# SIK-DIP-board.net
KiCad netlist of a schematic drawn in EAGLE
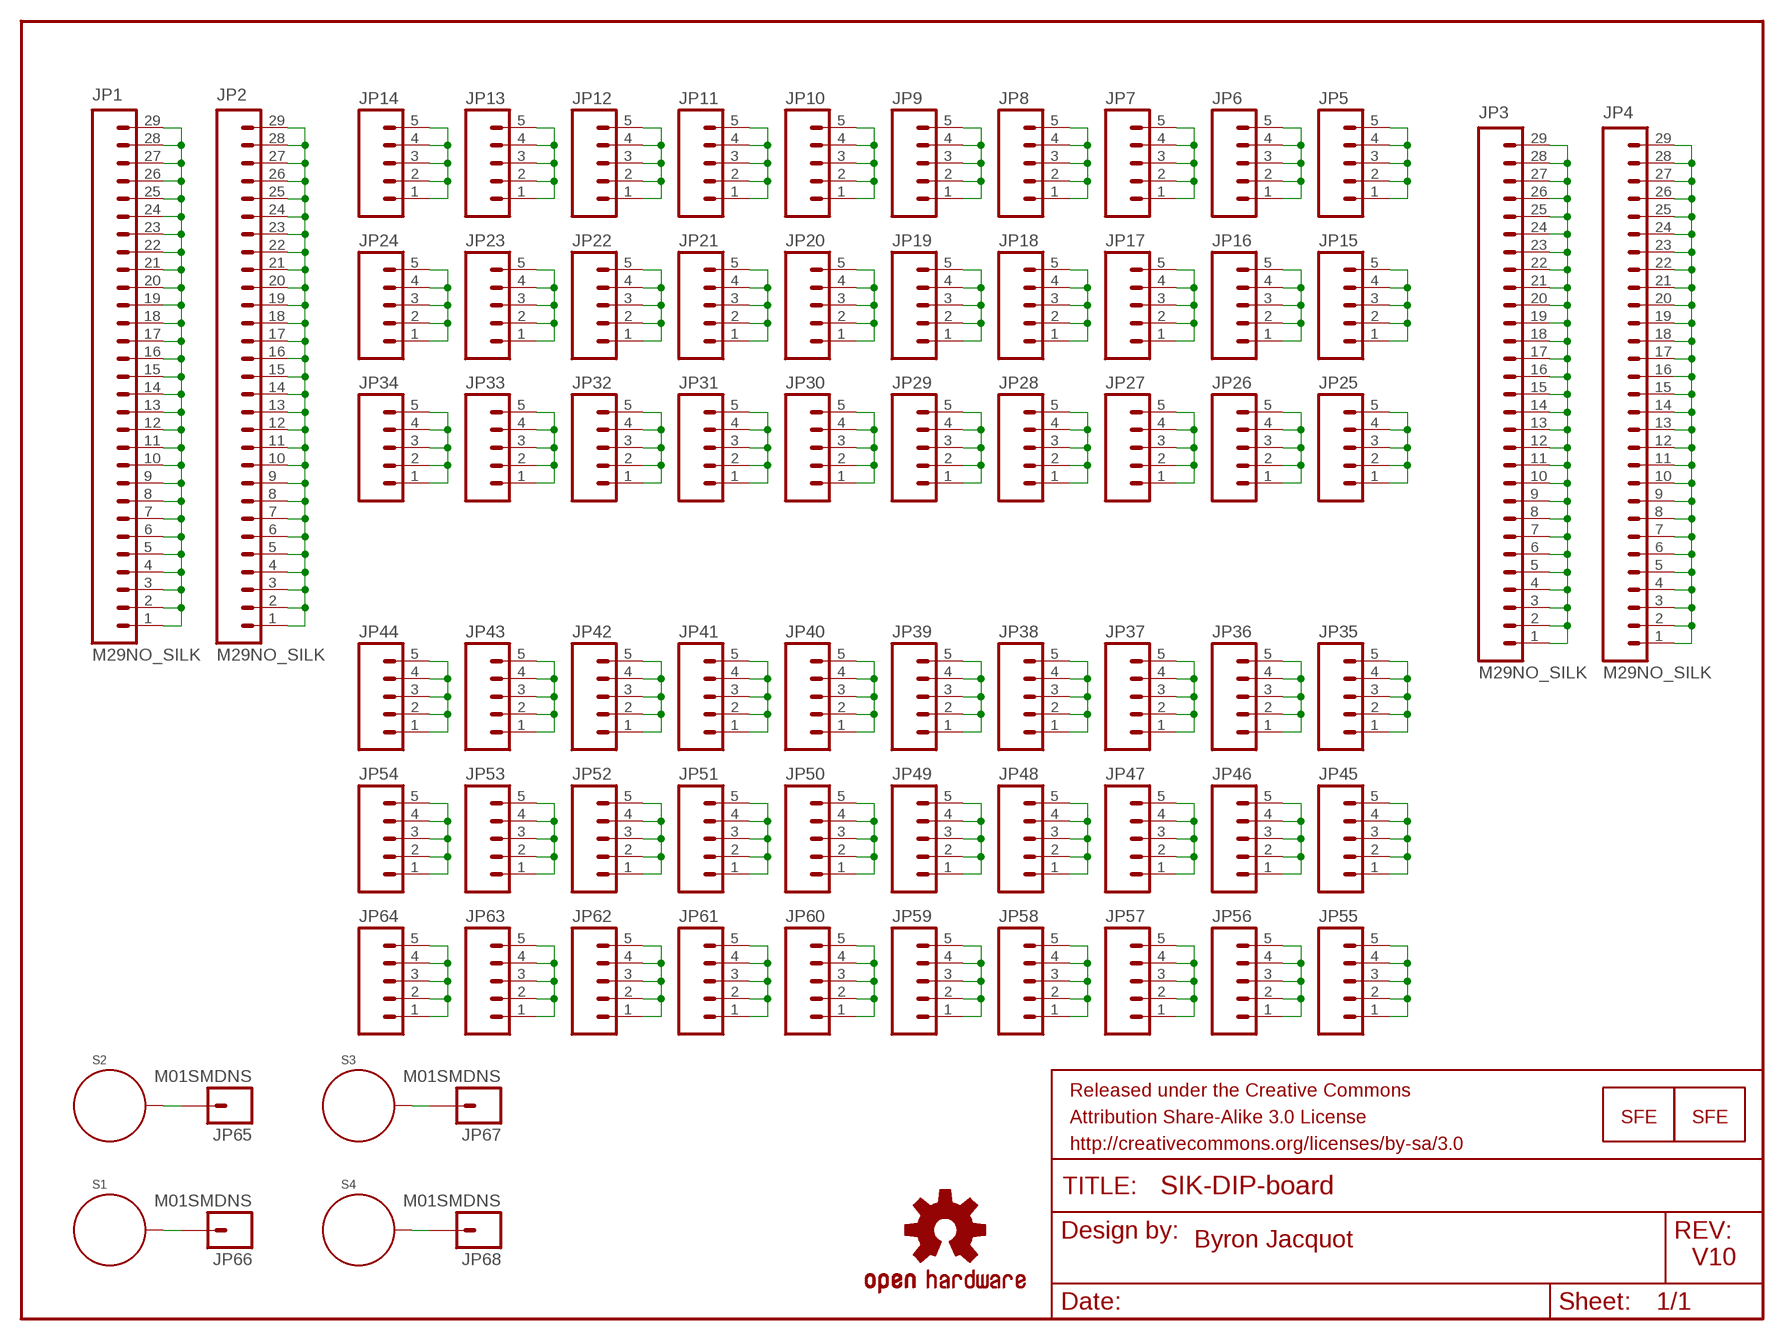
[diagram p0: schematic, sheet 1]

(export (version "E")
  (design (tool "Eeschema 10.0.6"))
  (components
    (comp (ref "FRAME1")
      (value "FRAME-LETTER")
      (footprint "eagle-import:CREATIVE_COMMONS")
      (libsource (lib "eagle-import") (part "FRAME-LETTER"))
    )
    (comp (ref "JP1")
      (value "M29NO_SILK")
      (footprint "eagle-import:1X29_NO_SILK")
      (libsource (lib "eagle-import") (part "M29NO_SILK"))
    )
    (comp (ref "JP2")
      (value "M29NO_SILK")
      (footprint "eagle-import:1X29_NO_SILK")
      (libsource (lib "eagle-import") (part "M29NO_SILK"))
    )
    (comp (ref "JP3")
      (value "M29NO_SILK")
      (footprint "eagle-import:1X29_NO_SILK")
      (libsource (lib "eagle-import") (part "M29NO_SILK"))
    )
    (comp (ref "JP4")
      (value "M29NO_SILK")
      (footprint "eagle-import:1X29_NO_SILK")
      (libsource (lib "eagle-import") (part "M29NO_SILK"))
    )
    (comp (ref "JP5")
      (value "M05NO_SILK")
      (footprint "eagle-import:1X05_NO_SILK")
      (libsource (lib "eagle-import") (part "M05NO_SILK"))
    )
    (comp (ref "JP6")
      (value "M05NO_SILK")
      (footprint "eagle-import:1X05_NO_SILK")
      (libsource (lib "eagle-import") (part "M05NO_SILK"))
    )
    (comp (ref "JP7")
      (value "M05NO_SILK")
      (footprint "eagle-import:1X05_NO_SILK")
      (libsource (lib "eagle-import") (part "M05NO_SILK"))
    )
    (comp (ref "JP8")
      (value "M05NO_SILK")
      (footprint "eagle-import:1X05_NO_SILK")
      (libsource (lib "eagle-import") (part "M05NO_SILK"))
    )
    (comp (ref "JP9")
      (value "M05NO_SILK")
      (footprint "eagle-import:1X05_NO_SILK")
      (libsource (lib "eagle-import") (part "M05NO_SILK"))
    )
    (comp (ref "JP10")
      (value "M05NO_SILK")
      (footprint "eagle-import:1X05_NO_SILK")
      (libsource (lib "eagle-import") (part "M05NO_SILK"))
    )
    (comp (ref "JP11")
      (value "M05NO_SILK")
      (footprint "eagle-import:1X05_NO_SILK")
      (libsource (lib "eagle-import") (part "M05NO_SILK"))
    )
    (comp (ref "JP12")
      (value "M05NO_SILK")
      (footprint "eagle-import:1X05_NO_SILK")
      (libsource (lib "eagle-import") (part "M05NO_SILK"))
    )
    (comp (ref "JP13")
      (value "M05NO_SILK")
      (footprint "eagle-import:1X05_NO_SILK")
      (libsource (lib "eagle-import") (part "M05NO_SILK"))
    )
    (comp (ref "JP14")
      (value "M05NO_SILK")
      (footprint "eagle-import:1X05_NO_SILK")
      (libsource (lib "eagle-import") (part "M05NO_SILK"))
    )
    (comp (ref "JP15")
      (value "M05NO_SILK")
      (footprint "eagle-import:1X05_NO_SILK")
      (libsource (lib "eagle-import") (part "M05NO_SILK"))
    )
    (comp (ref "JP16")
      (value "M05NO_SILK")
      (footprint "eagle-import:1X05_NO_SILK")
      (libsource (lib "eagle-import") (part "M05NO_SILK"))
    )
    (comp (ref "JP17")
      (value "M05NO_SILK")
      (footprint "eagle-import:1X05_NO_SILK")
      (libsource (lib "eagle-import") (part "M05NO_SILK"))
    )
    (comp (ref "JP18")
      (value "M05NO_SILK")
      (footprint "eagle-import:1X05_NO_SILK")
      (libsource (lib "eagle-import") (part "M05NO_SILK"))
    )
    (comp (ref "JP19")
      (value "M05NO_SILK")
      (footprint "eagle-import:1X05_NO_SILK")
      (libsource (lib "eagle-import") (part "M05NO_SILK"))
    )
    (comp (ref "JP20")
      (value "M05NO_SILK")
      (footprint "eagle-import:1X05_NO_SILK")
      (libsource (lib "eagle-import") (part "M05NO_SILK"))
    )
    (comp (ref "JP21")
      (value "M05NO_SILK")
      (footprint "eagle-import:1X05_NO_SILK")
      (libsource (lib "eagle-import") (part "M05NO_SILK"))
    )
    (comp (ref "JP22")
      (value "M05NO_SILK")
      (footprint "eagle-import:1X05_NO_SILK")
      (libsource (lib "eagle-import") (part "M05NO_SILK"))
    )
    (comp (ref "JP23")
      (value "M05NO_SILK")
      (footprint "eagle-import:1X05_NO_SILK")
      (libsource (lib "eagle-import") (part "M05NO_SILK"))
    )
    (comp (ref "JP24")
      (value "M05NO_SILK")
      (footprint "eagle-import:1X05_NO_SILK")
      (libsource (lib "eagle-import") (part "M05NO_SILK"))
    )
    (comp (ref "JP25")
      (value "M05NO_SILK")
      (footprint "eagle-import:1X05_NO_SILK")
      (libsource (lib "eagle-import") (part "M05NO_SILK"))
    )
    (comp (ref "JP26")
      (value "M05NO_SILK")
      (footprint "eagle-import:1X05_NO_SILK")
      (libsource (lib "eagle-import") (part "M05NO_SILK"))
    )
    (comp (ref "JP27")
      (value "M05NO_SILK")
      (footprint "eagle-import:1X05_NO_SILK")
      (libsource (lib "eagle-import") (part "M05NO_SILK"))
    )
    (comp (ref "JP28")
      (value "M05NO_SILK")
      (footprint "eagle-import:1X05_NO_SILK")
      (libsource (lib "eagle-import") (part "M05NO_SILK"))
    )
    (comp (ref "JP29")
      (value "M05NO_SILK")
      (footprint "eagle-import:1X05_NO_SILK")
      (libsource (lib "eagle-import") (part "M05NO_SILK"))
    )
    (comp (ref "JP30")
      (value "M05NO_SILK")
      (footprint "eagle-import:1X05_NO_SILK")
      (libsource (lib "eagle-import") (part "M05NO_SILK"))
    )
    (comp (ref "JP31")
      (value "M05NO_SILK")
      (footprint "eagle-import:1X05_NO_SILK")
      (libsource (lib "eagle-import") (part "M05NO_SILK"))
    )
    (comp (ref "JP32")
      (value "M05NO_SILK")
      (footprint "eagle-import:1X05_NO_SILK")
      (libsource (lib "eagle-import") (part "M05NO_SILK"))
    )
    (comp (ref "JP33")
      (value "M05NO_SILK")
      (footprint "eagle-import:1X05_NO_SILK")
      (libsource (lib "eagle-import") (part "M05NO_SILK"))
    )
    (comp (ref "JP34")
      (value "M05NO_SILK")
      (footprint "eagle-import:1X05_NO_SILK")
      (libsource (lib "eagle-import") (part "M05NO_SILK"))
    )
    (comp (ref "JP35")
      (value "M05NO_SILK")
      (footprint "eagle-import:1X05_NO_SILK")
      (libsource (lib "eagle-import") (part "M05NO_SILK"))
    )
    (comp (ref "JP36")
      (value "M05NO_SILK")
      (footprint "eagle-import:1X05_NO_SILK")
      (libsource (lib "eagle-import") (part "M05NO_SILK"))
    )
    (comp (ref "JP37")
      (value "M05NO_SILK")
      (footprint "eagle-import:1X05_NO_SILK")
      (libsource (lib "eagle-import") (part "M05NO_SILK"))
    )
    (comp (ref "JP38")
      (value "M05NO_SILK")
      (footprint "eagle-import:1X05_NO_SILK")
      (libsource (lib "eagle-import") (part "M05NO_SILK"))
    )
    (comp (ref "JP39")
      (value "M05NO_SILK")
      (footprint "eagle-import:1X05_NO_SILK")
      (libsource (lib "eagle-import") (part "M05NO_SILK"))
    )
    (comp (ref "JP40")
      (value "M05NO_SILK")
      (footprint "eagle-import:1X05_NO_SILK")
      (libsource (lib "eagle-import") (part "M05NO_SILK"))
    )
    (comp (ref "JP41")
      (value "M05NO_SILK")
      (footprint "eagle-import:1X05_NO_SILK")
      (libsource (lib "eagle-import") (part "M05NO_SILK"))
    )
    (comp (ref "JP42")
      (value "M05NO_SILK")
      (footprint "eagle-import:1X05_NO_SILK")
      (libsource (lib "eagle-import") (part "M05NO_SILK"))
    )
    (comp (ref "JP43")
      (value "M05NO_SILK")
      (footprint "eagle-import:1X05_NO_SILK")
      (libsource (lib "eagle-import") (part "M05NO_SILK"))
    )
    (comp (ref "JP44")
      (value "M05NO_SILK")
      (footprint "eagle-import:1X05_NO_SILK")
      (libsource (lib "eagle-import") (part "M05NO_SILK"))
    )
    (comp (ref "JP45")
      (value "M05NO_SILK")
      (footprint "eagle-import:1X05_NO_SILK")
      (libsource (lib "eagle-import") (part "M05NO_SILK"))
    )
    (comp (ref "JP46")
      (value "M05NO_SILK")
      (footprint "eagle-import:1X05_NO_SILK")
      (libsource (lib "eagle-import") (part "M05NO_SILK"))
    )
    (comp (ref "JP47")
      (value "M05NO_SILK")
      (footprint "eagle-import:1X05_NO_SILK")
      (libsource (lib "eagle-import") (part "M05NO_SILK"))
    )
    (comp (ref "JP48")
      (value "M05NO_SILK")
      (footprint "eagle-import:1X05_NO_SILK")
      (libsource (lib "eagle-import") (part "M05NO_SILK"))
    )
    (comp (ref "JP49")
      (value "M05NO_SILK")
      (footprint "eagle-import:1X05_NO_SILK")
      (libsource (lib "eagle-import") (part "M05NO_SILK"))
    )
    (comp (ref "JP50")
      (value "M05NO_SILK")
      (footprint "eagle-import:1X05_NO_SILK")
      (libsource (lib "eagle-import") (part "M05NO_SILK"))
    )
    (comp (ref "JP51")
      (value "M05NO_SILK")
      (footprint "eagle-import:1X05_NO_SILK")
      (libsource (lib "eagle-import") (part "M05NO_SILK"))
    )
    (comp (ref "JP52")
      (value "M05NO_SILK")
      (footprint "eagle-import:1X05_NO_SILK")
      (libsource (lib "eagle-import") (part "M05NO_SILK"))
    )
    (comp (ref "JP53")
      (value "M05NO_SILK")
      (footprint "eagle-import:1X05_NO_SILK")
      (libsource (lib "eagle-import") (part "M05NO_SILK"))
    )
    (comp (ref "JP54")
      (value "M05NO_SILK")
      (footprint "eagle-import:1X05_NO_SILK")
      (libsource (lib "eagle-import") (part "M05NO_SILK"))
    )
    (comp (ref "JP55")
      (value "M05NO_SILK")
      (footprint "eagle-import:1X05_NO_SILK")
      (libsource (lib "eagle-import") (part "M05NO_SILK"))
    )
    (comp (ref "JP56")
      (value "M05NO_SILK")
      (footprint "eagle-import:1X05_NO_SILK")
      (libsource (lib "eagle-import") (part "M05NO_SILK"))
    )
    (comp (ref "JP57")
      (value "M05NO_SILK")
      (footprint "eagle-import:1X05_NO_SILK")
      (libsource (lib "eagle-import") (part "M05NO_SILK"))
    )
    (comp (ref "JP58")
      (value "M05NO_SILK")
      (footprint "eagle-import:1X05_NO_SILK")
      (libsource (lib "eagle-import") (part "M05NO_SILK"))
    )
    (comp (ref "JP59")
      (value "M05NO_SILK")
      (footprint "eagle-import:1X05_NO_SILK")
      (libsource (lib "eagle-import") (part "M05NO_SILK"))
    )
    (comp (ref "JP60")
      (value "M05NO_SILK")
      (footprint "eagle-import:1X05_NO_SILK")
      (libsource (lib "eagle-import") (part "M05NO_SILK"))
    )
    (comp (ref "JP61")
      (value "M05NO_SILK")
      (footprint "eagle-import:1X05_NO_SILK")
      (libsource (lib "eagle-import") (part "M05NO_SILK"))
    )
    (comp (ref "JP62")
      (value "M05NO_SILK")
      (footprint "eagle-import:1X05_NO_SILK")
      (libsource (lib "eagle-import") (part "M05NO_SILK"))
    )
    (comp (ref "JP63")
      (value "M05NO_SILK")
      (footprint "eagle-import:1X05_NO_SILK")
      (libsource (lib "eagle-import") (part "M05NO_SILK"))
    )
    (comp (ref "JP64")
      (value "M05NO_SILK")
      (footprint "eagle-import:1X05_NO_SILK")
      (libsource (lib "eagle-import") (part "M05NO_SILK"))
    )
    (comp (ref "JP65")
      (value "M01SMDNS")
      (footprint "eagle-import:1X01NS")
      (libsource (lib "eagle-import") (part "M01SMDNS"))
    )
    (comp (ref "JP66")
      (value "M01SMDNS")
      (footprint "eagle-import:1X01NS")
      (libsource (lib "eagle-import") (part "M01SMDNS"))
    )
    (comp (ref "JP67")
      (value "M01SMDNS")
      (footprint "eagle-import:1X01NS")
      (libsource (lib "eagle-import") (part "M01SMDNS"))
    )
    (comp (ref "JP68")
      (value "M01SMDNS")
      (footprint "eagle-import:1X01NS")
      (libsource (lib "eagle-import") (part "M01SMDNS"))
    )
    (comp (ref "LOGO1")
      (value "LOGO-SFECP")
      (footprint "eagle-import:SFE-LOGO-FLAME-COPPER")
      (libsource (lib "eagle-import") (part "LOGO-SFECP"))
    )
    (comp (ref "LOGO2")
      (value "LOGO-SFENEW")
      (footprint "eagle-import:SFE-NEW-WEBLOGO")
      (libsource (lib "eagle-import") (part "LOGO-SFENEW"))
    )
    (comp (ref "LOGO3")
      (value "OSHW-LOGOS")
      (footprint "eagle-import:OSHW-LOGO-S")
      (libsource (lib "eagle-import") (part "OSHW-LOGOS"))
    )
    (comp (ref "S1")
      (value "STANDOFF_ELECTRICAL")
      (footprint "eagle-import:STANDOFF-ELECTRICAL")
      (libsource (lib "eagle-import") (part "STANDOFF_ELECTRICAL"))
    )
    (comp (ref "S2")
      (value "STANDOFF_ELECTRICAL")
      (footprint "eagle-import:STANDOFF-ELECTRICAL")
      (libsource (lib "eagle-import") (part "STANDOFF_ELECTRICAL"))
    )
    (comp (ref "S3")
      (value "STANDOFF_ELECTRICAL")
      (footprint "eagle-import:STANDOFF-ELECTRICAL")
      (libsource (lib "eagle-import") (part "STANDOFF_ELECTRICAL"))
    )
    (comp (ref "S4")
      (value "STANDOFF_ELECTRICAL")
      (footprint "eagle-import:STANDOFF-ELECTRICAL")
      (libsource (lib "eagle-import") (part "STANDOFF_ELECTRICAL"))
    )
  )
  (nets
    (net (code "1") (name "Net-(JP1-Pad1)") (class "Default")
      (node (ref "JP1") (pin "1") (pinfunction "1_1") (pintype "passive"))
      (node (ref "JP1") (pin "10") (pinfunction "10_10") (pintype "passive"))
      (node (ref "JP1") (pin "11") (pinfunction "11_11") (pintype "passive"))
      (node (ref "JP1") (pin "12") (pinfunction "12_12") (pintype "passive"))
      (node (ref "JP1") (pin "13") (pinfunction "13_13") (pintype "passive"))
      (node (ref "JP1") (pin "14") (pinfunction "14_14") (pintype "passive"))
      (node (ref "JP1") (pin "15") (pinfunction "15_15") (pintype "passive"))
      (node (ref "JP1") (pin "16") (pinfunction "16_16") (pintype "passive"))
      (node (ref "JP1") (pin "17") (pinfunction "17_17") (pintype "passive"))
      (node (ref "JP1") (pin "18") (pinfunction "18_18") (pintype "passive"))
      (node (ref "JP1") (pin "19") (pinfunction "19_19") (pintype "passive"))
      (node (ref "JP1") (pin "2") (pinfunction "2_2") (pintype "passive"))
      (node (ref "JP1") (pin "20") (pinfunction "20_20") (pintype "passive"))
      (node (ref "JP1") (pin "21") (pinfunction "21_21") (pintype "passive"))
      (node (ref "JP1") (pin "22") (pinfunction "22_22") (pintype "passive"))
      (node (ref "JP1") (pin "23") (pinfunction "23_23") (pintype "passive"))
      (node (ref "JP1") (pin "24") (pinfunction "24_24") (pintype "passive"))
      (node (ref "JP1") (pin "25") (pinfunction "25_25") (pintype "passive"))
      (node (ref "JP1") (pin "26") (pinfunction "26_26") (pintype "passive"))
      (node (ref "JP1") (pin "27") (pinfunction "27_27") (pintype "passive"))
      (node (ref "JP1") (pin "28") (pinfunction "28_28") (pintype "passive"))
      (node (ref "JP1") (pin "29") (pinfunction "29_29") (pintype "passive"))
      (node (ref "JP1") (pin "3") (pinfunction "3_3") (pintype "passive"))
      (node (ref "JP1") (pin "4") (pinfunction "4_4") (pintype "passive"))
      (node (ref "JP1") (pin "5") (pinfunction "5_5") (pintype "passive"))
      (node (ref "JP1") (pin "6") (pinfunction "6_6") (pintype "passive"))
      (node (ref "JP1") (pin "7") (pinfunction "7_7") (pintype "passive"))
      (node (ref "JP1") (pin "8") (pinfunction "8_8") (pintype "passive"))
      (node (ref "JP1") (pin "9") (pinfunction "9_9") (pintype "passive"))
    )
    (net (code "2") (name "Net-(JP2-Pad1)") (class "Default")
      (node (ref "JP2") (pin "1") (pinfunction "1_1") (pintype "passive"))
      (node (ref "JP2") (pin "10") (pinfunction "10_10") (pintype "passive"))
      (node (ref "JP2") (pin "11") (pinfunction "11_11") (pintype "passive"))
      (node (ref "JP2") (pin "12") (pinfunction "12_12") (pintype "passive"))
      (node (ref "JP2") (pin "13") (pinfunction "13_13") (pintype "passive"))
      (node (ref "JP2") (pin "14") (pinfunction "14_14") (pintype "passive"))
      (node (ref "JP2") (pin "15") (pinfunction "15_15") (pintype "passive"))
      (node (ref "JP2") (pin "16") (pinfunction "16_16") (pintype "passive"))
      (node (ref "JP2") (pin "17") (pinfunction "17_17") (pintype "passive"))
      (node (ref "JP2") (pin "18") (pinfunction "18_18") (pintype "passive"))
      (node (ref "JP2") (pin "19") (pinfunction "19_19") (pintype "passive"))
      (node (ref "JP2") (pin "2") (pinfunction "2_2") (pintype "passive"))
      (node (ref "JP2") (pin "20") (pinfunction "20_20") (pintype "passive"))
      (node (ref "JP2") (pin "21") (pinfunction "21_21") (pintype "passive"))
      (node (ref "JP2") (pin "22") (pinfunction "22_22") (pintype "passive"))
      (node (ref "JP2") (pin "23") (pinfunction "23_23") (pintype "passive"))
      (node (ref "JP2") (pin "24") (pinfunction "24_24") (pintype "passive"))
      (node (ref "JP2") (pin "25") (pinfunction "25_25") (pintype "passive"))
      (node (ref "JP2") (pin "26") (pinfunction "26_26") (pintype "passive"))
      (node (ref "JP2") (pin "27") (pinfunction "27_27") (pintype "passive"))
      (node (ref "JP2") (pin "28") (pinfunction "28_28") (pintype "passive"))
      (node (ref "JP2") (pin "29") (pinfunction "29_29") (pintype "passive"))
      (node (ref "JP2") (pin "3") (pinfunction "3_3") (pintype "passive"))
      (node (ref "JP2") (pin "4") (pinfunction "4_4") (pintype "passive"))
      (node (ref "JP2") (pin "5") (pinfunction "5_5") (pintype "passive"))
      (node (ref "JP2") (pin "6") (pinfunction "6_6") (pintype "passive"))
      (node (ref "JP2") (pin "7") (pinfunction "7_7") (pintype "passive"))
      (node (ref "JP2") (pin "8") (pinfunction "8_8") (pintype "passive"))
      (node (ref "JP2") (pin "9") (pinfunction "9_9") (pintype "passive"))
    )
    (net (code "3") (name "Net-(JP3-Pad1)") (class "Default")
      (node (ref "JP3") (pin "1") (pinfunction "1_1") (pintype "passive"))
      (node (ref "JP3") (pin "10") (pinfunction "10_10") (pintype "passive"))
      (node (ref "JP3") (pin "11") (pinfunction "11_11") (pintype "passive"))
      (node (ref "JP3") (pin "12") (pinfunction "12_12") (pintype "passive"))
      (node (ref "JP3") (pin "13") (pinfunction "13_13") (pintype "passive"))
      (node (ref "JP3") (pin "14") (pinfunction "14_14") (pintype "passive"))
      (node (ref "JP3") (pin "15") (pinfunction "15_15") (pintype "passive"))
      (node (ref "JP3") (pin "16") (pinfunction "16_16") (pintype "passive"))
      (node (ref "JP3") (pin "17") (pinfunction "17_17") (pintype "passive"))
      (node (ref "JP3") (pin "18") (pinfunction "18_18") (pintype "passive"))
      (node (ref "JP3") (pin "19") (pinfunction "19_19") (pintype "passive"))
      (node (ref "JP3") (pin "2") (pinfunction "2_2") (pintype "passive"))
      (node (ref "JP3") (pin "20") (pinfunction "20_20") (pintype "passive"))
      (node (ref "JP3") (pin "21") (pinfunction "21_21") (pintype "passive"))
      (node (ref "JP3") (pin "22") (pinfunction "22_22") (pintype "passive"))
      (node (ref "JP3") (pin "23") (pinfunction "23_23") (pintype "passive"))
      (node (ref "JP3") (pin "24") (pinfunction "24_24") (pintype "passive"))
      (node (ref "JP3") (pin "25") (pinfunction "25_25") (pintype "passive"))
      (node (ref "JP3") (pin "26") (pinfunction "26_26") (pintype "passive"))
      (node (ref "JP3") (pin "27") (pinfunction "27_27") (pintype "passive"))
      (node (ref "JP3") (pin "28") (pinfunction "28_28") (pintype "passive"))
      (node (ref "JP3") (pin "29") (pinfunction "29_29") (pintype "passive"))
      (node (ref "JP3") (pin "3") (pinfunction "3_3") (pintype "passive"))
      (node (ref "JP3") (pin "4") (pinfunction "4_4") (pintype "passive"))
      (node (ref "JP3") (pin "5") (pinfunction "5_5") (pintype "passive"))
      (node (ref "JP3") (pin "6") (pinfunction "6_6") (pintype "passive"))
      (node (ref "JP3") (pin "7") (pinfunction "7_7") (pintype "passive"))
      (node (ref "JP3") (pin "8") (pinfunction "8_8") (pintype "passive"))
      (node (ref "JP3") (pin "9") (pinfunction "9_9") (pintype "passive"))
    )
    (net (code "4") (name "Net-(JP4-Pad1)") (class "Default")
      (node (ref "JP4") (pin "1") (pinfunction "1_1") (pintype "passive"))
      (node (ref "JP4") (pin "10") (pinfunction "10_10") (pintype "passive"))
      (node (ref "JP4") (pin "11") (pinfunction "11_11") (pintype "passive"))
      (node (ref "JP4") (pin "12") (pinfunction "12_12") (pintype "passive"))
      (node (ref "JP4") (pin "13") (pinfunction "13_13") (pintype "passive"))
      (node (ref "JP4") (pin "14") (pinfunction "14_14") (pintype "passive"))
      (node (ref "JP4") (pin "15") (pinfunction "15_15") (pintype "passive"))
      (node (ref "JP4") (pin "16") (pinfunction "16_16") (pintype "passive"))
      (node (ref "JP4") (pin "17") (pinfunction "17_17") (pintype "passive"))
      (node (ref "JP4") (pin "18") (pinfunction "18_18") (pintype "passive"))
      (node (ref "JP4") (pin "19") (pinfunction "19_19") (pintype "passive"))
      (node (ref "JP4") (pin "2") (pinfunction "2_2") (pintype "passive"))
      (node (ref "JP4") (pin "20") (pinfunction "20_20") (pintype "passive"))
      (node (ref "JP4") (pin "21") (pinfunction "21_21") (pintype "passive"))
      (node (ref "JP4") (pin "22") (pinfunction "22_22") (pintype "passive"))
      (node (ref "JP4") (pin "23") (pinfunction "23_23") (pintype "passive"))
      (node (ref "JP4") (pin "24") (pinfunction "24_24") (pintype "passive"))
      (node (ref "JP4") (pin "25") (pinfunction "25_25") (pintype "passive"))
      (node (ref "JP4") (pin "26") (pinfunction "26_26") (pintype "passive"))
      (node (ref "JP4") (pin "27") (pinfunction "27_27") (pintype "passive"))
      (node (ref "JP4") (pin "28") (pinfunction "28_28") (pintype "passive"))
      (node (ref "JP4") (pin "29") (pinfunction "29_29") (pintype "passive"))
      (node (ref "JP4") (pin "3") (pinfunction "3_3") (pintype "passive"))
      (node (ref "JP4") (pin "4") (pinfunction "4_4") (pintype "passive"))
      (node (ref "JP4") (pin "5") (pinfunction "5_5") (pintype "passive"))
      (node (ref "JP4") (pin "6") (pinfunction "6_6") (pintype "passive"))
      (node (ref "JP4") (pin "7") (pinfunction "7_7") (pintype "passive"))
      (node (ref "JP4") (pin "8") (pinfunction "8_8") (pintype "passive"))
      (node (ref "JP4") (pin "9") (pinfunction "9_9") (pintype "passive"))
    )
    (net (code "5") (name "Net-(JP5-Pad1)") (class "Default")
      (node (ref "JP5") (pin "1") (pinfunction "1_1") (pintype "passive"))
      (node (ref "JP5") (pin "2") (pinfunction "2_2") (pintype "passive"))
      (node (ref "JP5") (pin "3") (pinfunction "3_3") (pintype "passive"))
      (node (ref "JP5") (pin "4") (pinfunction "4_4") (pintype "passive"))
      (node (ref "JP5") (pin "5") (pinfunction "5_5") (pintype "passive"))
    )
    (net (code "6") (name "Net-(JP6-Pad1)") (class "Default")
      (node (ref "JP6") (pin "1") (pinfunction "1_1") (pintype "passive"))
      (node (ref "JP6") (pin "2") (pinfunction "2_2") (pintype "passive"))
      (node (ref "JP6") (pin "3") (pinfunction "3_3") (pintype "passive"))
      (node (ref "JP6") (pin "4") (pinfunction "4_4") (pintype "passive"))
      (node (ref "JP6") (pin "5") (pinfunction "5_5") (pintype "passive"))
    )
    (net (code "7") (name "Net-(JP7-Pad1)") (class "Default")
      (node (ref "JP7") (pin "1") (pinfunction "1_1") (pintype "passive"))
      (node (ref "JP7") (pin "2") (pinfunction "2_2") (pintype "passive"))
      (node (ref "JP7") (pin "3") (pinfunction "3_3") (pintype "passive"))
      (node (ref "JP7") (pin "4") (pinfunction "4_4") (pintype "passive"))
      (node (ref "JP7") (pin "5") (pinfunction "5_5") (pintype "passive"))
    )
    (net (code "8") (name "Net-(JP8-Pad1)") (class "Default")
      (node (ref "JP8") (pin "1") (pinfunction "1_1") (pintype "passive"))
      (node (ref "JP8") (pin "2") (pinfunction "2_2") (pintype "passive"))
      (node (ref "JP8") (pin "3") (pinfunction "3_3") (pintype "passive"))
      (node (ref "JP8") (pin "4") (pinfunction "4_4") (pintype "passive"))
      (node (ref "JP8") (pin "5") (pinfunction "5_5") (pintype "passive"))
    )
    (net (code "9") (name "Net-(JP9-Pad1)") (class "Default")
      (node (ref "JP9") (pin "1") (pinfunction "1_1") (pintype "passive"))
      (node (ref "JP9") (pin "2") (pinfunction "2_2") (pintype "passive"))
      (node (ref "JP9") (pin "3") (pinfunction "3_3") (pintype "passive"))
      (node (ref "JP9") (pin "4") (pinfunction "4_4") (pintype "passive"))
      (node (ref "JP9") (pin "5") (pinfunction "5_5") (pintype "passive"))
    )
    (net (code "10") (name "Net-(JP10-Pad1)") (class "Default")
      (node (ref "JP10") (pin "1") (pinfunction "1_1") (pintype "passive"))
      (node (ref "JP10") (pin "2") (pinfunction "2_2") (pintype "passive"))
      (node (ref "JP10") (pin "3") (pinfunction "3_3") (pintype "passive"))
      (node (ref "JP10") (pin "4") (pinfunction "4_4") (pintype "passive"))
      (node (ref "JP10") (pin "5") (pinfunction "5_5") (pintype "passive"))
    )
    (net (code "11") (name "Net-(JP11-Pad1)") (class "Default")
      (node (ref "JP11") (pin "1") (pinfunction "1_1") (pintype "passive"))
      (node (ref "JP11") (pin "2") (pinfunction "2_2") (pintype "passive"))
      (node (ref "JP11") (pin "3") (pinfunction "3_3") (pintype "passive"))
      (node (ref "JP11") (pin "4") (pinfunction "4_4") (pintype "passive"))
      (node (ref "JP11") (pin "5") (pinfunction "5_5") (pintype "passive"))
    )
    (net (code "12") (name "Net-(JP12-Pad1)") (class "Default")
      (node (ref "JP12") (pin "1") (pinfunction "1_1") (pintype "passive"))
      (node (ref "JP12") (pin "2") (pinfunction "2_2") (pintype "passive"))
      (node (ref "JP12") (pin "3") (pinfunction "3_3") (pintype "passive"))
      (node (ref "JP12") (pin "4") (pinfunction "4_4") (pintype "passive"))
      (node (ref "JP12") (pin "5") (pinfunction "5_5") (pintype "passive"))
    )
    (net (code "13") (name "Net-(JP13-Pad1)") (class "Default")
      (node (ref "JP13") (pin "1") (pinfunction "1_1") (pintype "passive"))
      (node (ref "JP13") (pin "2") (pinfunction "2_2") (pintype "passive"))
      (node (ref "JP13") (pin "3") (pinfunction "3_3") (pintype "passive"))
      (node (ref "JP13") (pin "4") (pinfunction "4_4") (pintype "passive"))
      (node (ref "JP13") (pin "5") (pinfunction "5_5") (pintype "passive"))
    )
    (net (code "14") (name "Net-(JP14-Pad1)") (class "Default")
      (node (ref "JP14") (pin "1") (pinfunction "1_1") (pintype "passive"))
      (node (ref "JP14") (pin "2") (pinfunction "2_2") (pintype "passive"))
      (node (ref "JP14") (pin "3") (pinfunction "3_3") (pintype "passive"))
      (node (ref "JP14") (pin "4") (pinfunction "4_4") (pintype "passive"))
      (node (ref "JP14") (pin "5") (pinfunction "5_5") (pintype "passive"))
    )
    (net (code "15") (name "Net-(JP15-Pad1)") (class "Default")
      (node (ref "JP15") (pin "1") (pinfunction "1_1") (pintype "passive"))
      (node (ref "JP15") (pin "2") (pinfunction "2_2") (pintype "passive"))
      (node (ref "JP15") (pin "3") (pinfunction "3_3") (pintype "passive"))
      (node (ref "JP15") (pin "4") (pinfunction "4_4") (pintype "passive"))
      (node (ref "JP15") (pin "5") (pinfunction "5_5") (pintype "passive"))
    )
    (net (code "16") (name "Net-(JP16-Pad1)") (class "Default")
      (node (ref "JP16") (pin "1") (pinfunction "1_1") (pintype "passive"))
      (node (ref "JP16") (pin "2") (pinfunction "2_2") (pintype "passive"))
      (node (ref "JP16") (pin "3") (pinfunction "3_3") (pintype "passive"))
      (node (ref "JP16") (pin "4") (pinfunction "4_4") (pintype "passive"))
      (node (ref "JP16") (pin "5") (pinfunction "5_5") (pintype "passive"))
    )
    (net (code "17") (name "Net-(JP17-Pad1)") (class "Default")
      (node (ref "JP17") (pin "1") (pinfunction "1_1") (pintype "passive"))
      (node (ref "JP17") (pin "2") (pinfunction "2_2") (pintype "passive"))
      (node (ref "JP17") (pin "3") (pinfunction "3_3") (pintype "passive"))
      (node (ref "JP17") (pin "4") (pinfunction "4_4") (pintype "passive"))
      (node (ref "JP17") (pin "5") (pinfunction "5_5") (pintype "passive"))
    )
    (net (code "18") (name "Net-(JP18-Pad1)") (class "Default")
      (node (ref "JP18") (pin "1") (pinfunction "1_1") (pintype "passive"))
      (node (ref "JP18") (pin "2") (pinfunction "2_2") (pintype "passive"))
      (node (ref "JP18") (pin "3") (pinfunction "3_3") (pintype "passive"))
      (node (ref "JP18") (pin "4") (pinfunction "4_4") (pintype "passive"))
      (node (ref "JP18") (pin "5") (pinfunction "5_5") (pintype "passive"))
    )
    (net (code "19") (name "Net-(JP19-Pad1)") (class "Default")
      (node (ref "JP19") (pin "1") (pinfunction "1_1") (pintype "passive"))
      (node (ref "JP19") (pin "2") (pinfunction "2_2") (pintype "passive"))
      (node (ref "JP19") (pin "3") (pinfunction "3_3") (pintype "passive"))
      (node (ref "JP19") (pin "4") (pinfunction "4_4") (pintype "passive"))
      (node (ref "JP19") (pin "5") (pinfunction "5_5") (pintype "passive"))
    )
    (net (code "20") (name "Net-(JP20-Pad1)") (class "Default")
      (node (ref "JP20") (pin "1") (pinfunction "1_1") (pintype "passive"))
      (node (ref "JP20") (pin "2") (pinfunction "2_2") (pintype "passive"))
      (node (ref "JP20") (pin "3") (pinfunction "3_3") (pintype "passive"))
      (node (ref "JP20") (pin "4") (pinfunction "4_4") (pintype "passive"))
      (node (ref "JP20") (pin "5") (pinfunction "5_5") (pintype "passive"))
    )
    (net (code "21") (name "Net-(JP21-Pad1)") (class "Default")
      (node (ref "JP21") (pin "1") (pinfunction "1_1") (pintype "passive"))
      (node (ref "JP21") (pin "2") (pinfunction "2_2") (pintype "passive"))
      (node (ref "JP21") (pin "3") (pinfunction "3_3") (pintype "passive"))
      (node (ref "JP21") (pin "4") (pinfunction "4_4") (pintype "passive"))
      (node (ref "JP21") (pin "5") (pinfunction "5_5") (pintype "passive"))
    )
    (net (code "22") (name "Net-(JP22-Pad1)") (class "Default")
      (node (ref "JP22") (pin "1") (pinfunction "1_1") (pintype "passive"))
      (node (ref "JP22") (pin "2") (pinfunction "2_2") (pintype "passive"))
      (node (ref "JP22") (pin "3") (pinfunction "3_3") (pintype "passive"))
      (node (ref "JP22") (pin "4") (pinfunction "4_4") (pintype "passive"))
      (node (ref "JP22") (pin "5") (pinfunction "5_5") (pintype "passive"))
    )
    (net (code "23") (name "Net-(JP23-Pad1)") (class "Default")
      (node (ref "JP23") (pin "1") (pinfunction "1_1") (pintype "passive"))
      (node (ref "JP23") (pin "2") (pinfunction "2_2") (pintype "passive"))
      (node (ref "JP23") (pin "3") (pinfunction "3_3") (pintype "passive"))
      (node (ref "JP23") (pin "4") (pinfunction "4_4") (pintype "passive"))
      (node (ref "JP23") (pin "5") (pinfunction "5_5") (pintype "passive"))
    )
    (net (code "24") (name "Net-(JP24-Pad1)") (class "Default")
      (node (ref "JP24") (pin "1") (pinfunction "1_1") (pintype "passive"))
      (node (ref "JP24") (pin "2") (pinfunction "2_2") (pintype "passive"))
      (node (ref "JP24") (pin "3") (pinfunction "3_3") (pintype "passive"))
      (node (ref "JP24") (pin "4") (pinfunction "4_4") (pintype "passive"))
      (node (ref "JP24") (pin "5") (pinfunction "5_5") (pintype "passive"))
    )
    (net (code "25") (name "Net-(JP25-Pad1)") (class "Default")
      (node (ref "JP25") (pin "1") (pinfunction "1_1") (pintype "passive"))
      (node (ref "JP25") (pin "2") (pinfunction "2_2") (pintype "passive"))
      (node (ref "JP25") (pin "3") (pinfunction "3_3") (pintype "passive"))
      (node (ref "JP25") (pin "4") (pinfunction "4_4") (pintype "passive"))
      (node (ref "JP25") (pin "5") (pinfunction "5_5") (pintype "passive"))
    )
    (net (code "26") (name "Net-(JP26-Pad1)") (class "Default")
      (node (ref "JP26") (pin "1") (pinfunction "1_1") (pintype "passive"))
      (node (ref "JP26") (pin "2") (pinfunction "2_2") (pintype "passive"))
      (node (ref "JP26") (pin "3") (pinfunction "3_3") (pintype "passive"))
      (node (ref "JP26") (pin "4") (pinfunction "4_4") (pintype "passive"))
      (node (ref "JP26") (pin "5") (pinfunction "5_5") (pintype "passive"))
    )
    (net (code "27") (name "Net-(JP27-Pad1)") (class "Default")
      (node (ref "JP27") (pin "1") (pinfunction "1_1") (pintype "passive"))
      (node (ref "JP27") (pin "2") (pinfunction "2_2") (pintype "passive"))
      (node (ref "JP27") (pin "3") (pinfunction "3_3") (pintype "passive"))
      (node (ref "JP27") (pin "4") (pinfunction "4_4") (pintype "passive"))
      (node (ref "JP27") (pin "5") (pinfunction "5_5") (pintype "passive"))
    )
    (net (code "28") (name "Net-(JP28-Pad1)") (class "Default")
      (node (ref "JP28") (pin "1") (pinfunction "1_1") (pintype "passive"))
      (node (ref "JP28") (pin "2") (pinfunction "2_2") (pintype "passive"))
      (node (ref "JP28") (pin "3") (pinfunction "3_3") (pintype "passive"))
      (node (ref "JP28") (pin "4") (pinfunction "4_4") (pintype "passive"))
      (node (ref "JP28") (pin "5") (pinfunction "5_5") (pintype "passive"))
    )
    (net (code "29") (name "Net-(JP29-Pad1)") (class "Default")
      (node (ref "JP29") (pin "1") (pinfunction "1_1") (pintype "passive"))
      (node (ref "JP29") (pin "2") (pinfunction "2_2") (pintype "passive"))
      (node (ref "JP29") (pin "3") (pinfunction "3_3") (pintype "passive"))
      (node (ref "JP29") (pin "4") (pinfunction "4_4") (pintype "passive"))
      (node (ref "JP29") (pin "5") (pinfunction "5_5") (pintype "passive"))
    )
    (net (code "30") (name "Net-(JP30-Pad1)") (class "Default")
      (node (ref "JP30") (pin "1") (pinfunction "1_1") (pintype "passive"))
      (node (ref "JP30") (pin "2") (pinfunction "2_2") (pintype "passive"))
      (node (ref "JP30") (pin "3") (pinfunction "3_3") (pintype "passive"))
      (node (ref "JP30") (pin "4") (pinfunction "4_4") (pintype "passive"))
      (node (ref "JP30") (pin "5") (pinfunction "5_5") (pintype "passive"))
    )
    (net (code "31") (name "Net-(JP31-Pad1)") (class "Default")
      (node (ref "JP31") (pin "1") (pinfunction "1_1") (pintype "passive"))
      (node (ref "JP31") (pin "2") (pinfunction "2_2") (pintype "passive"))
      (node (ref "JP31") (pin "3") (pinfunction "3_3") (pintype "passive"))
      (node (ref "JP31") (pin "4") (pinfunction "4_4") (pintype "passive"))
      (node (ref "JP31") (pin "5") (pinfunction "5_5") (pintype "passive"))
    )
    (net (code "32") (name "Net-(JP32-Pad1)") (class "Default")
      (node (ref "JP32") (pin "1") (pinfunction "1_1") (pintype "passive"))
      (node (ref "JP32") (pin "2") (pinfunction "2_2") (pintype "passive"))
      (node (ref "JP32") (pin "3") (pinfunction "3_3") (pintype "passive"))
      (node (ref "JP32") (pin "4") (pinfunction "4_4") (pintype "passive"))
      (node (ref "JP32") (pin "5") (pinfunction "5_5") (pintype "passive"))
    )
    (net (code "33") (name "Net-(JP33-Pad1)") (class "Default")
      (node (ref "JP33") (pin "1") (pinfunction "1_1") (pintype "passive"))
      (node (ref "JP33") (pin "2") (pinfunction "2_2") (pintype "passive"))
      (node (ref "JP33") (pin "3") (pinfunction "3_3") (pintype "passive"))
      (node (ref "JP33") (pin "4") (pinfunction "4_4") (pintype "passive"))
      (node (ref "JP33") (pin "5") (pinfunction "5_5") (pintype "passive"))
    )
    (net (code "34") (name "Net-(JP34-Pad1)") (class "Default")
      (node (ref "JP34") (pin "1") (pinfunction "1_1") (pintype "passive"))
      (node (ref "JP34") (pin "2") (pinfunction "2_2") (pintype "passive"))
      (node (ref "JP34") (pin "3") (pinfunction "3_3") (pintype "passive"))
      (node (ref "JP34") (pin "4") (pinfunction "4_4") (pintype "passive"))
      (node (ref "JP34") (pin "5") (pinfunction "5_5") (pintype "passive"))
    )
    (net (code "35") (name "Net-(JP35-Pad1)") (class "Default")
      (node (ref "JP35") (pin "1") (pinfunction "1_1") (pintype "passive"))
      (node (ref "JP35") (pin "2") (pinfunction "2_2") (pintype "passive"))
      (node (ref "JP35") (pin "3") (pinfunction "3_3") (pintype "passive"))
      (node (ref "JP35") (pin "4") (pinfunction "4_4") (pintype "passive"))
      (node (ref "JP35") (pin "5") (pinfunction "5_5") (pintype "passive"))
    )
    (net (code "36") (name "Net-(JP36-Pad1)") (class "Default")
      (node (ref "JP36") (pin "1") (pinfunction "1_1") (pintype "passive"))
      (node (ref "JP36") (pin "2") (pinfunction "2_2") (pintype "passive"))
      (node (ref "JP36") (pin "3") (pinfunction "3_3") (pintype "passive"))
      (node (ref "JP36") (pin "4") (pinfunction "4_4") (pintype "passive"))
      (node (ref "JP36") (pin "5") (pinfunction "5_5") (pintype "passive"))
    )
    (net (code "37") (name "Net-(JP37-Pad1)") (class "Default")
      (node (ref "JP37") (pin "1") (pinfunction "1_1") (pintype "passive"))
      (node (ref "JP37") (pin "2") (pinfunction "2_2") (pintype "passive"))
      (node (ref "JP37") (pin "3") (pinfunction "3_3") (pintype "passive"))
      (node (ref "JP37") (pin "4") (pinfunction "4_4") (pintype "passive"))
      (node (ref "JP37") (pin "5") (pinfunction "5_5") (pintype "passive"))
    )
    (net (code "38") (name "Net-(JP38-Pad1)") (class "Default")
      (node (ref "JP38") (pin "1") (pinfunction "1_1") (pintype "passive"))
      (node (ref "JP38") (pin "2") (pinfunction "2_2") (pintype "passive"))
      (node (ref "JP38") (pin "3") (pinfunction "3_3") (pintype "passive"))
      (node (ref "JP38") (pin "4") (pinfunction "4_4") (pintype "passive"))
      (node (ref "JP38") (pin "5") (pinfunction "5_5") (pintype "passive"))
    )
    (net (code "39") (name "Net-(JP39-Pad1)") (class "Default")
      (node (ref "JP39") (pin "1") (pinfunction "1_1") (pintype "passive"))
      (node (ref "JP39") (pin "2") (pinfunction "2_2") (pintype "passive"))
      (node (ref "JP39") (pin "3") (pinfunction "3_3") (pintype "passive"))
      (node (ref "JP39") (pin "4") (pinfunction "4_4") (pintype "passive"))
      (node (ref "JP39") (pin "5") (pinfunction "5_5") (pintype "passive"))
    )
    (net (code "40") (name "Net-(JP40-Pad1)") (class "Default")
      (node (ref "JP40") (pin "1") (pinfunction "1_1") (pintype "passive"))
      (node (ref "JP40") (pin "2") (pinfunction "2_2") (pintype "passive"))
      (node (ref "JP40") (pin "3") (pinfunction "3_3") (pintype "passive"))
      (node (ref "JP40") (pin "4") (pinfunction "4_4") (pintype "passive"))
      (node (ref "JP40") (pin "5") (pinfunction "5_5") (pintype "passive"))
    )
    (net (code "41") (name "Net-(JP41-Pad1)") (class "Default")
      (node (ref "JP41") (pin "1") (pinfunction "1_1") (pintype "passive"))
      (node (ref "JP41") (pin "2") (pinfunction "2_2") (pintype "passive"))
      (node (ref "JP41") (pin "3") (pinfunction "3_3") (pintype "passive"))
      (node (ref "JP41") (pin "4") (pinfunction "4_4") (pintype "passive"))
      (node (ref "JP41") (pin "5") (pinfunction "5_5") (pintype "passive"))
    )
    (net (code "42") (name "Net-(JP42-Pad1)") (class "Default")
      (node (ref "JP42") (pin "1") (pinfunction "1_1") (pintype "passive"))
      (node (ref "JP42") (pin "2") (pinfunction "2_2") (pintype "passive"))
      (node (ref "JP42") (pin "3") (pinfunction "3_3") (pintype "passive"))
      (node (ref "JP42") (pin "4") (pinfunction "4_4") (pintype "passive"))
      (node (ref "JP42") (pin "5") (pinfunction "5_5") (pintype "passive"))
    )
    (net (code "43") (name "Net-(JP43-Pad1)") (class "Default")
      (node (ref "JP43") (pin "1") (pinfunction "1_1") (pintype "passive"))
      (node (ref "JP43") (pin "2") (pinfunction "2_2") (pintype "passive"))
      (node (ref "JP43") (pin "3") (pinfunction "3_3") (pintype "passive"))
      (node (ref "JP43") (pin "4") (pinfunction "4_4") (pintype "passive"))
      (node (ref "JP43") (pin "5") (pinfunction "5_5") (pintype "passive"))
    )
    (net (code "44") (name "Net-(JP44-Pad1)") (class "Default")
      (node (ref "JP44") (pin "1") (pinfunction "1_1") (pintype "passive"))
      (node (ref "JP44") (pin "2") (pinfunction "2_2") (pintype "passive"))
      (node (ref "JP44") (pin "3") (pinfunction "3_3") (pintype "passive"))
      (node (ref "JP44") (pin "4") (pinfunction "4_4") (pintype "passive"))
      (node (ref "JP44") (pin "5") (pinfunction "5_5") (pintype "passive"))
    )
    (net (code "45") (name "Net-(JP45-Pad1)") (class "Default")
      (node (ref "JP45") (pin "1") (pinfunction "1_1") (pintype "passive"))
      (node (ref "JP45") (pin "2") (pinfunction "2_2") (pintype "passive"))
      (node (ref "JP45") (pin "3") (pinfunction "3_3") (pintype "passive"))
      (node (ref "JP45") (pin "4") (pinfunction "4_4") (pintype "passive"))
      (node (ref "JP45") (pin "5") (pinfunction "5_5") (pintype "passive"))
    )
    (net (code "46") (name "Net-(JP46-Pad1)") (class "Default")
      (node (ref "JP46") (pin "1") (pinfunction "1_1") (pintype "passive"))
      (node (ref "JP46") (pin "2") (pinfunction "2_2") (pintype "passive"))
      (node (ref "JP46") (pin "3") (pinfunction "3_3") (pintype "passive"))
      (node (ref "JP46") (pin "4") (pinfunction "4_4") (pintype "passive"))
      (node (ref "JP46") (pin "5") (pinfunction "5_5") (pintype "passive"))
    )
    (net (code "47") (name "Net-(JP47-Pad1)") (class "Default")
      (node (ref "JP47") (pin "1") (pinfunction "1_1") (pintype "passive"))
      (node (ref "JP47") (pin "2") (pinfunction "2_2") (pintype "passive"))
      (node (ref "JP47") (pin "3") (pinfunction "3_3") (pintype "passive"))
      (node (ref "JP47") (pin "4") (pinfunction "4_4") (pintype "passive"))
      (node (ref "JP47") (pin "5") (pinfunction "5_5") (pintype "passive"))
    )
    (net (code "48") (name "Net-(JP48-Pad1)") (class "Default")
      (node (ref "JP48") (pin "1") (pinfunction "1_1") (pintype "passive"))
      (node (ref "JP48") (pin "2") (pinfunction "2_2") (pintype "passive"))
      (node (ref "JP48") (pin "3") (pinfunction "3_3") (pintype "passive"))
      (node (ref "JP48") (pin "4") (pinfunction "4_4") (pintype "passive"))
      (node (ref "JP48") (pin "5") (pinfunction "5_5") (pintype "passive"))
    )
    (net (code "49") (name "Net-(JP49-Pad1)") (class "Default")
      (node (ref "JP49") (pin "1") (pinfunction "1_1") (pintype "passive"))
      (node (ref "JP49") (pin "2") (pinfunction "2_2") (pintype "passive"))
      (node (ref "JP49") (pin "3") (pinfunction "3_3") (pintype "passive"))
      (node (ref "JP49") (pin "4") (pinfunction "4_4") (pintype "passive"))
      (node (ref "JP49") (pin "5") (pinfunction "5_5") (pintype "passive"))
    )
    (net (code "50") (name "Net-(JP50-Pad1)") (class "Default")
      (node (ref "JP50") (pin "1") (pinfunction "1_1") (pintype "passive"))
      (node (ref "JP50") (pin "2") (pinfunction "2_2") (pintype "passive"))
      (node (ref "JP50") (pin "3") (pinfunction "3_3") (pintype "passive"))
      (node (ref "JP50") (pin "4") (pinfunction "4_4") (pintype "passive"))
      (node (ref "JP50") (pin "5") (pinfunction "5_5") (pintype "passive"))
    )
    (net (code "51") (name "Net-(JP51-Pad1)") (class "Default")
      (node (ref "JP51") (pin "1") (pinfunction "1_1") (pintype "passive"))
      (node (ref "JP51") (pin "2") (pinfunction "2_2") (pintype "passive"))
      (node (ref "JP51") (pin "3") (pinfunction "3_3") (pintype "passive"))
      (node (ref "JP51") (pin "4") (pinfunction "4_4") (pintype "passive"))
      (node (ref "JP51") (pin "5") (pinfunction "5_5") (pintype "passive"))
    )
    (net (code "52") (name "Net-(JP52-Pad1)") (class "Default")
      (node (ref "JP52") (pin "1") (pinfunction "1_1") (pintype "passive"))
      (node (ref "JP52") (pin "2") (pinfunction "2_2") (pintype "passive"))
      (node (ref "JP52") (pin "3") (pinfunction "3_3") (pintype "passive"))
      (node (ref "JP52") (pin "4") (pinfunction "4_4") (pintype "passive"))
      (node (ref "JP52") (pin "5") (pinfunction "5_5") (pintype "passive"))
    )
    (net (code "53") (name "Net-(JP53-Pad1)") (class "Default")
      (node (ref "JP53") (pin "1") (pinfunction "1_1") (pintype "passive"))
      (node (ref "JP53") (pin "2") (pinfunction "2_2") (pintype "passive"))
      (node (ref "JP53") (pin "3") (pinfunction "3_3") (pintype "passive"))
      (node (ref "JP53") (pin "4") (pinfunction "4_4") (pintype "passive"))
      (node (ref "JP53") (pin "5") (pinfunction "5_5") (pintype "passive"))
    )
    (net (code "54") (name "Net-(JP54-Pad1)") (class "Default")
      (node (ref "JP54") (pin "1") (pinfunction "1_1") (pintype "passive"))
      (node (ref "JP54") (pin "2") (pinfunction "2_2") (pintype "passive"))
      (node (ref "JP54") (pin "3") (pinfunction "3_3") (pintype "passive"))
      (node (ref "JP54") (pin "4") (pinfunction "4_4") (pintype "passive"))
      (node (ref "JP54") (pin "5") (pinfunction "5_5") (pintype "passive"))
    )
    (net (code "55") (name "Net-(JP55-Pad1)") (class "Default")
      (node (ref "JP55") (pin "1") (pinfunction "1_1") (pintype "passive"))
      (node (ref "JP55") (pin "2") (pinfunction "2_2") (pintype "passive"))
      (node (ref "JP55") (pin "3") (pinfunction "3_3") (pintype "passive"))
      (node (ref "JP55") (pin "4") (pinfunction "4_4") (pintype "passive"))
      (node (ref "JP55") (pin "5") (pinfunction "5_5") (pintype "passive"))
    )
    (net (code "56") (name "Net-(JP56-Pad1)") (class "Default")
      (node (ref "JP56") (pin "1") (pinfunction "1_1") (pintype "passive"))
      (node (ref "JP56") (pin "2") (pinfunction "2_2") (pintype "passive"))
      (node (ref "JP56") (pin "3") (pinfunction "3_3") (pintype "passive"))
      (node (ref "JP56") (pin "4") (pinfunction "4_4") (pintype "passive"))
      (node (ref "JP56") (pin "5") (pinfunction "5_5") (pintype "passive"))
    )
    (net (code "57") (name "Net-(JP57-Pad1)") (class "Default")
      (node (ref "JP57") (pin "1") (pinfunction "1_1") (pintype "passive"))
      (node (ref "JP57") (pin "2") (pinfunction "2_2") (pintype "passive"))
      (node (ref "JP57") (pin "3") (pinfunction "3_3") (pintype "passive"))
      (node (ref "JP57") (pin "4") (pinfunction "4_4") (pintype "passive"))
      (node (ref "JP57") (pin "5") (pinfunction "5_5") (pintype "passive"))
    )
    (net (code "58") (name "Net-(JP58-Pad1)") (class "Default")
      (node (ref "JP58") (pin "1") (pinfunction "1_1") (pintype "passive"))
      (node (ref "JP58") (pin "2") (pinfunction "2_2") (pintype "passive"))
      (node (ref "JP58") (pin "3") (pinfunction "3_3") (pintype "passive"))
      (node (ref "JP58") (pin "4") (pinfunction "4_4") (pintype "passive"))
      (node (ref "JP58") (pin "5") (pinfunction "5_5") (pintype "passive"))
    )
    (net (code "59") (name "Net-(JP59-Pad1)") (class "Default")
      (node (ref "JP59") (pin "1") (pinfunction "1_1") (pintype "passive"))
      (node (ref "JP59") (pin "2") (pinfunction "2_2") (pintype "passive"))
      (node (ref "JP59") (pin "3") (pinfunction "3_3") (pintype "passive"))
      (node (ref "JP59") (pin "4") (pinfunction "4_4") (pintype "passive"))
      (node (ref "JP59") (pin "5") (pinfunction "5_5") (pintype "passive"))
    )
    (net (code "60") (name "Net-(JP60-Pad1)") (class "Default")
      (node (ref "JP60") (pin "1") (pinfunction "1_1") (pintype "passive"))
      (node (ref "JP60") (pin "2") (pinfunction "2_2") (pintype "passive"))
      (node (ref "JP60") (pin "3") (pinfunction "3_3") (pintype "passive"))
      (node (ref "JP60") (pin "4") (pinfunction "4_4") (pintype "passive"))
      (node (ref "JP60") (pin "5") (pinfunction "5_5") (pintype "passive"))
    )
    (net (code "61") (name "Net-(JP61-Pad1)") (class "Default")
      (node (ref "JP61") (pin "1") (pinfunction "1_1") (pintype "passive"))
      (node (ref "JP61") (pin "2") (pinfunction "2_2") (pintype "passive"))
      (node (ref "JP61") (pin "3") (pinfunction "3_3") (pintype "passive"))
      (node (ref "JP61") (pin "4") (pinfunction "4_4") (pintype "passive"))
      (node (ref "JP61") (pin "5") (pinfunction "5_5") (pintype "passive"))
    )
    (net (code "62") (name "Net-(JP62-Pad1)") (class "Default")
      (node (ref "JP62") (pin "1") (pinfunction "1_1") (pintype "passive"))
      (node (ref "JP62") (pin "2") (pinfunction "2_2") (pintype "passive"))
      (node (ref "JP62") (pin "3") (pinfunction "3_3") (pintype "passive"))
      (node (ref "JP62") (pin "4") (pinfunction "4_4") (pintype "passive"))
      (node (ref "JP62") (pin "5") (pinfunction "5_5") (pintype "passive"))
    )
    (net (code "63") (name "Net-(JP63-Pad1)") (class "Default")
      (node (ref "JP63") (pin "1") (pinfunction "1_1") (pintype "passive"))
      (node (ref "JP63") (pin "2") (pinfunction "2_2") (pintype "passive"))
      (node (ref "JP63") (pin "3") (pinfunction "3_3") (pintype "passive"))
      (node (ref "JP63") (pin "4") (pinfunction "4_4") (pintype "passive"))
      (node (ref "JP63") (pin "5") (pinfunction "5_5") (pintype "passive"))
    )
    (net (code "64") (name "Net-(JP64-Pad1)") (class "Default")
      (node (ref "JP64") (pin "1") (pinfunction "1_1") (pintype "passive"))
      (node (ref "JP64") (pin "2") (pinfunction "2_2") (pintype "passive"))
      (node (ref "JP64") (pin "3") (pinfunction "3_3") (pintype "passive"))
      (node (ref "JP64") (pin "4") (pinfunction "4_4") (pintype "passive"))
      (node (ref "JP64") (pin "5") (pinfunction "5_5") (pintype "passive"))
    )
    (net (code "65") (name "Net-(S1-P$1)") (class "Default")
      (node (ref "JP66") (pin "1") (pinfunction "1_1") (pintype "passive"))
      (node (ref "S1") (pin "P1") (pinfunction "P$1_P1") (pintype "bidirectional"))
    )
    (net (code "66") (name "Net-(S2-P$1)") (class "Default")
      (node (ref "JP65") (pin "1") (pinfunction "1_1") (pintype "passive"))
      (node (ref "S2") (pin "P1") (pinfunction "P$1_P1") (pintype "bidirectional"))
    )
    (net (code "67") (name "Net-(S3-P$1)") (class "Default")
      (node (ref "JP67") (pin "1") (pinfunction "1_1") (pintype "passive"))
      (node (ref "S3") (pin "P1") (pinfunction "P$1_P1") (pintype "bidirectional"))
    )
    (net (code "68") (name "Net-(S4-P$1)") (class "Default")
      (node (ref "JP68") (pin "1") (pinfunction "1_1") (pintype "passive"))
      (node (ref "S4") (pin "P1") (pinfunction "P$1_P1") (pintype "bidirectional"))
    )
  )
)
